# blinken-v2.net
KiCad netlist of a schematic drawn in EAGLE
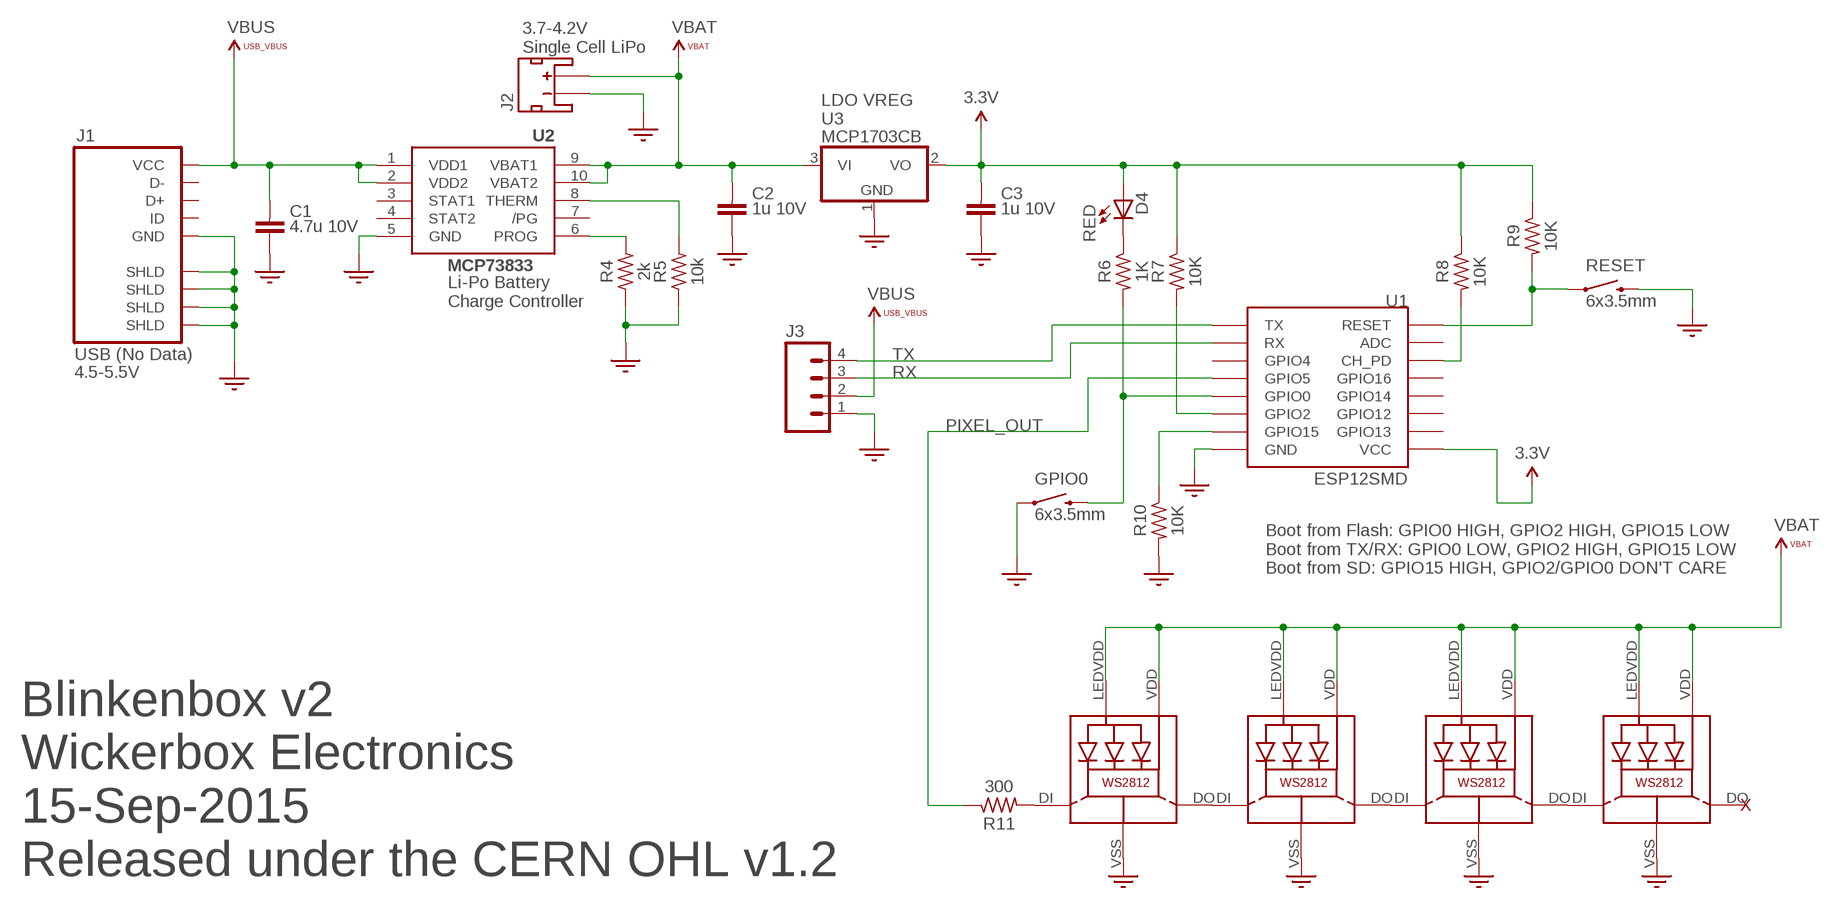
[diagram p0: schematic, sheet 1]

(export (version "E")
  (design (tool "Eeschema 10.0.6"))
  (components
    (comp (ref "C1")
      (value "4.7u 10V")
      (footprint "eagle-import:RLC-0805")
      (libsource (lib "eagle-import") (part "CAP-0805"))
    )
    (comp (ref "C2")
      (value "1u 10V")
      (footprint "eagle-import:RLC-0603")
      (libsource (lib "eagle-import") (part "CAP-0603"))
    )
    (comp (ref "C3")
      (value "1u 10V")
      (footprint "eagle-import:RLC-0603")
      (libsource (lib "eagle-import") (part "CAP-0603"))
    )
    (comp (ref "D4")
      (value "RED")
      (footprint "eagle-import:LED0603")
      (libsource (lib "eagle-import") (part "BG1111C"))
    )
    (comp (ref "GPIO0")
      (value "6x3.5mm")
      (footprint "eagle-import:TACTILE-SWITCH-1101NE")
      (libsource (lib "eagle-import") (part "SWITCH-MOMENTARY-2SMD-1101NE"))
    )
    (comp (ref "J1")
      (value "USB (No Data)")
      (footprint "eagle-import:ZX62D-B-5P8")
      (libsource (lib "eagle-import") (part "ZX62D-B-5P8"))
    )
    (comp (ref "J2")
      (value "JST_2MM_MALE")
      (footprint "eagle-import:JST-2-SMD")
      (libsource (lib "eagle-import") (part "JST_2MM_MALE"))
    )
    (comp (ref "J3")
      (value "M041X04_NO_SILK")
      (footprint "eagle-import:1X04_NO_SILK")
      (libsource (lib "eagle-import") (part "M041X04_NO_SILK"))
    )
    (comp (ref "LED1")
      (value "WS2812")
      (footprint "eagle-import:WS2812")
      (libsource (lib "eagle-import") (part "WS2812"))
    )
    (comp (ref "LED2")
      (value "WS2812")
      (footprint "eagle-import:WS2812")
      (libsource (lib "eagle-import") (part "WS2812"))
    )
    (comp (ref "LED3")
      (value "WS2812")
      (footprint "eagle-import:WS2812")
      (libsource (lib "eagle-import") (part "WS2812"))
    )
    (comp (ref "LED4")
      (value "WS2812")
      (footprint "eagle-import:WS2812")
      (libsource (lib "eagle-import") (part "WS2812"))
    )
    (comp (ref "R4")
      (value "2k")
      (footprint "eagle-import:RLC-0402")
      (libsource (lib "eagle-import") (part "RES-0402"))
    )
    (comp (ref "R5")
      (value "10k")
      (footprint "eagle-import:RLC-0402")
      (libsource (lib "eagle-import") (part "RES-0402"))
    )
    (comp (ref "R6")
      (value "1K")
      (footprint "eagle-import:RLC-0402")
      (libsource (lib "eagle-import") (part "RES-0402"))
    )
    (comp (ref "R7")
      (value "10K")
      (footprint "eagle-import:RLC-0402")
      (libsource (lib "eagle-import") (part "RES-0402"))
    )
    (comp (ref "R8")
      (value "10K")
      (footprint "eagle-import:RLC-0402")
      (libsource (lib "eagle-import") (part "RES-0402"))
    )
    (comp (ref "R9")
      (value "10K")
      (footprint "eagle-import:RLC-0402")
      (libsource (lib "eagle-import") (part "RES-0402"))
    )
    (comp (ref "R10")
      (value "10K")
      (footprint "eagle-import:RLC-0402")
      (libsource (lib "eagle-import") (part "RES-0402"))
    )
    (comp (ref "R11")
      (value "300")
      (footprint "eagle-import:RLC-0402")
      (libsource (lib "eagle-import") (part "RES-0402"))
    )
    (comp (ref "RESET")
      (value "6x3.5mm")
      (footprint "eagle-import:TACTILE-SWITCH-1101NE")
      (libsource (lib "eagle-import") (part "SWITCH-MOMENTARY-2SMD-1101NE"))
    )
    (comp (ref "U1")
      (value "ESP12SMD")
      (footprint "eagle-import:ESP12_SMD")
      (libsource (lib "eagle-import") (part "ESP12SMD"))
    )
    (comp (ref "U2")
      (value "MCP73833-UN")
      (footprint "eagle-import:MSOP10")
      (libsource (lib "eagle-import") (part "MCP73833-UN"))
    )
    (comp (ref "U3")
      (value "MCP1703CB")
      (footprint "eagle-import:SOT23")
      (libsource (lib "eagle-import") (part "MCP1703CB"))
    )
  )
  (nets
    (net (code "1") (name "/PIXEL_OUT") (class "Default")
      (node (ref "R11") (pin "1") (pinfunction "1_1") (pintype "passive"))
      (node (ref "U1") (pin "GPIO5") (pinfunction "GPIO5_GPIO5") (pintype "bidirectional"))
    )
    (net (code "2") (name "/RX") (class "Default")
      (node (ref "J3") (pin "3") (pinfunction "3_3") (pintype "passive"))
      (node (ref "U1") (pin "RX") (pinfunction "RX_RX") (pintype "bidirectional"))
    )
    (net (code "3") (name "/TX") (class "Default")
      (node (ref "J3") (pin "4") (pinfunction "4_4") (pintype "passive"))
      (node (ref "U1") (pin "TX") (pinfunction "TX_TX") (pintype "bidirectional"))
    )
    (net (code "4") (name "3.3V") (class "Default")
      (node (ref "C3") (pin "2") (pinfunction "1_2") (pintype "passive"))
      (node (ref "D4") (pin "A") (pinfunction "A_A") (pintype "passive"))
      (node (ref "R7") (pin "1") (pinfunction "1_1") (pintype "passive"))
      (node (ref "R8") (pin "1") (pinfunction "1_1") (pintype "passive"))
      (node (ref "R9") (pin "1") (pinfunction "1_1") (pintype "passive"))
      (node (ref "U1") (pin "VCC") (pinfunction "VCC_VCC") (pintype "bidirectional"))
      (node (ref "U3") (pin "2") (pinfunction "VO_2") (pintype "passive"))
    )
    (net (code "5") (name "GND") (class "Default")
      (node (ref "C1") (pin "2") (pinfunction "2_2") (pintype "passive"))
      (node (ref "C2") (pin "1") (pinfunction "2_1") (pintype "passive"))
      (node (ref "C3") (pin "1") (pinfunction "2_1") (pintype "passive"))
      (node (ref "GPIO0") (pin "1") (pinfunction "1_1") (pintype "passive"))
      (node (ref "J1") (pin "P$1") (pinfunction "SHLD_P$1") (pintype "power_in"))
      (node (ref "J1") (pin "P$2") (pinfunction "SHLD_P$2") (pintype "power_in"))
      (node (ref "J1") (pin "P$3") (pinfunction "SHLD_P$3") (pintype "power_in"))
      (node (ref "J1") (pin "P$4") (pinfunction "SHLD_P$4") (pintype "power_in"))
      (node (ref "J1") (pin "P5") (pinfunction "GND_P5") (pintype "power_in"))
      (node (ref "J2") (pin "1") (pinfunction "-_1") (pintype "bidirectional"))
      (node (ref "J3") (pin "1") (pinfunction "1_1") (pintype "passive"))
      (node (ref "LED1") (pin "VSS") (pinfunction "GND_VSS") (pintype "power_in"))
      (node (ref "LED2") (pin "VSS") (pinfunction "GND_VSS") (pintype "power_in"))
      (node (ref "LED3") (pin "VSS") (pinfunction "GND_VSS") (pintype "power_in"))
      (node (ref "LED4") (pin "VSS") (pinfunction "GND_VSS") (pintype "power_in"))
      (node (ref "R10") (pin "2") (pinfunction "2_2") (pintype "passive"))
      (node (ref "R4") (pin "1") (pinfunction "1_1") (pintype "passive"))
      (node (ref "R5") (pin "1") (pinfunction "1_1") (pintype "passive"))
      (node (ref "RESET") (pin "2") (pinfunction "2_2") (pintype "passive"))
      (node (ref "U1") (pin "GND") (pinfunction "GND_GND") (pintype "bidirectional"))
      (node (ref "U2") (pin "5") (pinfunction "GND_5") (pintype "power_in"))
      (node (ref "U3") (pin "1") (pinfunction "GND_1") (pintype "passive"))
    )
    (net (code "6") (name "Net-(D4-PadC)") (class "Default")
      (node (ref "D4") (pin "C") (pinfunction "C_C") (pintype "passive"))
      (node (ref "R6") (pin "1") (pinfunction "1_1") (pintype "passive"))
    )
    (net (code "7") (name "Net-(GPIO0-Pad2)") (class "Default")
      (node (ref "GPIO0") (pin "2") (pinfunction "2_2") (pintype "passive"))
      (node (ref "R6") (pin "2") (pinfunction "2_2") (pintype "passive"))
      (node (ref "U1") (pin "GPIO0") (pinfunction "GPIO0_GPIO0") (pintype "bidirectional"))
    )
    (net (code "8") (name "Net-(LED1-PadDI)") (class "Default")
      (node (ref "LED1") (pin "DI") (pinfunction "DI_DI") (pintype "input"))
      (node (ref "R11") (pin "2") (pinfunction "2_2") (pintype "passive"))
    )
    (net (code "9") (name "Net-(LED1-PadDO)") (class "Default")
      (node (ref "LED1") (pin "DO") (pinfunction "DO_DO") (pintype "output"))
      (node (ref "LED2") (pin "DI") (pinfunction "DI_DI") (pintype "input"))
    )
    (net (code "10") (name "Net-(LED2-PadDO)") (class "Default")
      (node (ref "LED2") (pin "DO") (pinfunction "DO_DO") (pintype "output"))
      (node (ref "LED3") (pin "DI") (pinfunction "DI_DI") (pintype "input"))
    )
    (net (code "11") (name "Net-(LED3-PadDO)") (class "Default")
      (node (ref "LED3") (pin "DO") (pinfunction "DO_DO") (pintype "output"))
      (node (ref "LED4") (pin "DI") (pinfunction "DI_DI") (pintype "input"))
    )
    (net (code "12") (name "Net-(R7-Pad2)") (class "Default")
      (node (ref "R7") (pin "2") (pinfunction "2_2") (pintype "passive"))
      (node (ref "U1") (pin "GPIO2") (pinfunction "GPIO2_GPIO2") (pintype "bidirectional"))
    )
    (net (code "13") (name "Net-(R8-Pad2)") (class "Default")
      (node (ref "R8") (pin "2") (pinfunction "2_2") (pintype "passive"))
      (node (ref "U1") (pin "CH_PD") (pinfunction "CH_PD_CH_PD") (pintype "bidirectional"))
    )
    (net (code "14") (name "Net-(R9-Pad2)") (class "Default")
      (node (ref "R9") (pin "2") (pinfunction "2_2") (pintype "passive"))
      (node (ref "RESET") (pin "1") (pinfunction "1_1") (pintype "passive"))
      (node (ref "U1") (pin "RESET") (pinfunction "RESET_RESET") (pintype "bidirectional"))
    )
    (net (code "15") (name "Net-(R10-Pad1)") (class "Default")
      (node (ref "R10") (pin "1") (pinfunction "1_1") (pintype "passive"))
      (node (ref "U1") (pin "GPIO15") (pinfunction "GPIO15_GPIO15") (pintype "bidirectional"))
    )
    (net (code "16") (name "Net-(U2-PROG)") (class "Default")
      (node (ref "R4") (pin "2") (pinfunction "2_2") (pintype "passive"))
      (node (ref "U2") (pin "6") (pinfunction "PROG_6") (pintype "input"))
    )
    (net (code "17") (name "Net-(U2-THERM)") (class "Default")
      (node (ref "R5") (pin "2") (pinfunction "2_2") (pintype "passive"))
      (node (ref "U2") (pin "8") (pinfunction "THERM_8") (pintype "bidirectional"))
    )
    (net (code "18") (name "VBAT") (class "Default")
      (node (ref "C2") (pin "2") (pinfunction "1_2") (pintype "passive"))
      (node (ref "J2") (pin "2") (pinfunction "+_2") (pintype "bidirectional"))
      (node (ref "LED1") (pin "LEDVDD") (pinfunction "LEDVDD_LEDVDD") (pintype "power_in"))
      (node (ref "LED1") (pin "VDD") (pinfunction "VDD_VDD") (pintype "power_in"))
      (node (ref "LED2") (pin "LEDVDD") (pinfunction "LEDVDD_LEDVDD") (pintype "power_in"))
      (node (ref "LED2") (pin "VDD") (pinfunction "VDD_VDD") (pintype "power_in"))
      (node (ref "LED3") (pin "LEDVDD") (pinfunction "LEDVDD_LEDVDD") (pintype "power_in"))
      (node (ref "LED3") (pin "VDD") (pinfunction "VDD_VDD") (pintype "power_in"))
      (node (ref "LED4") (pin "LEDVDD") (pinfunction "LEDVDD_LEDVDD") (pintype "power_in"))
      (node (ref "LED4") (pin "VDD") (pinfunction "VDD_VDD") (pintype "power_in"))
      (node (ref "U2") (pin "10") (pinfunction "VBAT2_10") (pintype "output"))
      (node (ref "U2") (pin "9") (pinfunction "VBAT1_9") (pintype "output"))
      (node (ref "U3") (pin "3") (pinfunction "VI_3") (pintype "input"))
    )
    (net (code "19") (name "VBUS") (class "Default")
      (node (ref "C1") (pin "1") (pinfunction "1_1") (pintype "passive"))
      (node (ref "J1") (pin "P1") (pinfunction "VCC_P1") (pintype "power_in"))
      (node (ref "J3") (pin "2") (pinfunction "2_2") (pintype "passive"))
      (node (ref "U2") (pin "1") (pinfunction "VDD1_1") (pintype "power_in"))
      (node (ref "U2") (pin "2") (pinfunction "VDD2_2") (pintype "power_in"))
    )
    (net (code "20") (name "unconnected-(J1-D+-PadP3)") (class "Default")
      (node (ref "J1") (pin "P3") (pinfunction "D+_P3") (pintype "bidirectional"))
    )
    (net (code "21") (name "unconnected-(J1-D--PadP2)") (class "Default")
      (node (ref "J1") (pin "P2") (pinfunction "D-_P2") (pintype "bidirectional"))
    )
    (net (code "22") (name "unconnected-(J1-ID-PadP4)") (class "Default")
      (node (ref "J1") (pin "P4") (pinfunction "ID_P4") (pintype "bidirectional"))
    )
    (net (code "23") (name "unconnected-(J2-PAD1-PadNC1)") (class "Default")
      (node (ref "J2") (pin "NC1") (pinfunction "PAD1_NC1") (pintype "bidirectional"))
    )
    (net (code "24") (name "unconnected-(J2-PAD2-PadNC2)") (class "Default")
      (node (ref "J2") (pin "NC2") (pinfunction "PAD2_NC2") (pintype "bidirectional"))
    )
    (net (code "25") (name "unconnected-(LED4-PadDO)") (class "Default")
      (node (ref "LED4") (pin "DO") (pinfunction "DO_DO") (pintype "output"))
    )
    (net (code "26") (name "unconnected-(U1-PadADC)") (class "Default")
      (node (ref "U1") (pin "ADC") (pinfunction "ADC_ADC") (pintype "bidirectional"))
    )
    (net (code "27") (name "unconnected-(U1-PadGPIO4)") (class "Default")
      (node (ref "U1") (pin "GPIO4") (pinfunction "GPIO4_GPIO4") (pintype "bidirectional"))
    )
    (net (code "28") (name "unconnected-(U1-PadGPIO12)") (class "Default")
      (node (ref "U1") (pin "GPIO12") (pinfunction "GPIO12_GPIO12") (pintype "bidirectional"))
    )
    (net (code "29") (name "unconnected-(U1-PadGPIO13)") (class "Default")
      (node (ref "U1") (pin "GPIO13") (pinfunction "GPIO13_GPIO13") (pintype "bidirectional"))
    )
    (net (code "30") (name "unconnected-(U1-PadGPIO14)") (class "Default")
      (node (ref "U1") (pin "GPIO14") (pinfunction "GPIO14_GPIO14") (pintype "bidirectional"))
    )
    (net (code "31") (name "unconnected-(U1-PadGPIO16)") (class "Default")
      (node (ref "U1") (pin "GPIO16") (pinfunction "GPIO16_GPIO16") (pintype "bidirectional"))
    )
    (net (code "32") (name "unconnected-(U2-STAT1-Pad3)") (class "Default")
      (node (ref "U2") (pin "3") (pinfunction "STAT1_3") (pintype "passive"))
    )
    (net (code "33") (name "unconnected-(U2-STAT2-Pad4)") (class "Default")
      (node (ref "U2") (pin "4") (pinfunction "STAT2_4") (pintype "passive"))
    )
    (net (code "34") (name "unconnected-(U2-{slash}PG-Pad7)") (class "Default")
      (node (ref "U2") (pin "7") (pinfunction "/PG_7") (pintype "passive"))
    )
  )
)
